# ledboard_smallcon.net
KiCad netlist of a schematic drawn in EAGLE
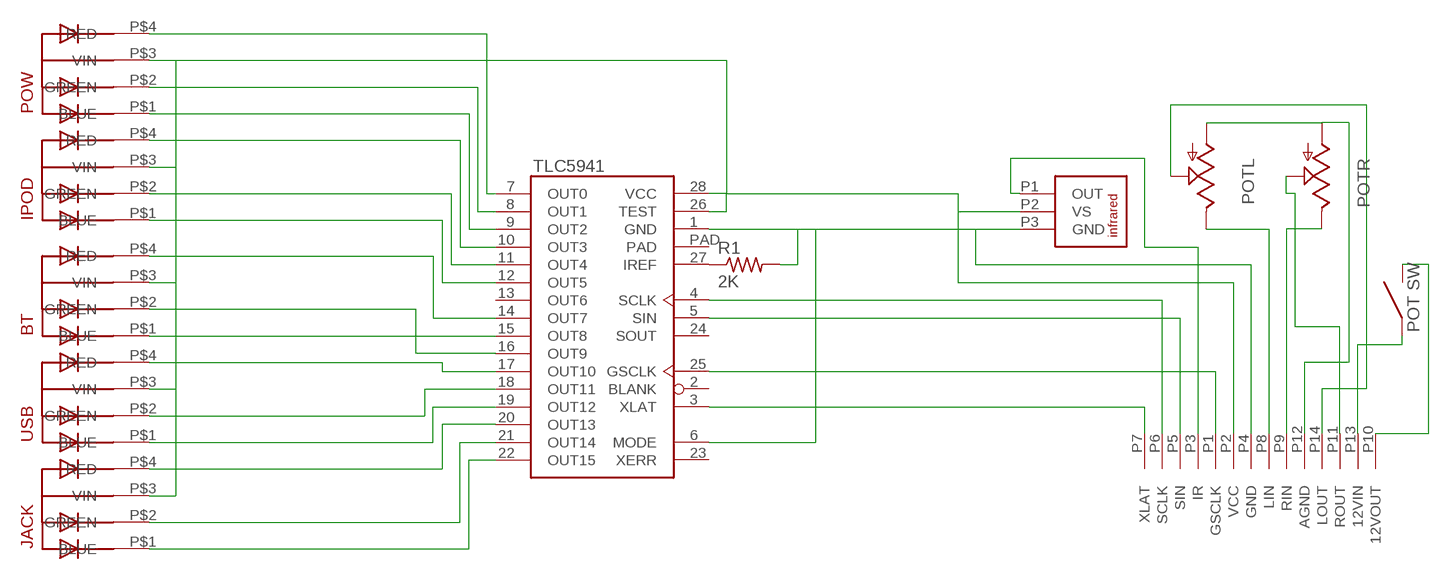
[diagram p0: schematic, sheet 1]

(export (version "E")
  (design (tool "Eeschema 10.0.6"))
  (components
    (comp (ref "BT")
      (value "5MMRGBLEDBENT")
      (footprint "eagle-import:BENTLED")
      (libsource (lib "eagle-import") (part "5MMRGBLEDBENT"))
    )
    (comp (ref "IPOD")
      (value "5MMRGBLEDBENT")
      (footprint "eagle-import:BENTLED")
      (libsource (lib "eagle-import") (part "5MMRGBLEDBENT"))
    )
    (comp (ref "IR")
      (value "TSOP323")
      (footprint "eagle-import:TSOP323")
      (libsource (lib "eagle-import") (part "TSOP323"))
    )
    (comp (ref "JACK")
      (value "5MMRGBLEDBENT")
      (footprint "eagle-import:BENTLED")
      (libsource (lib "eagle-import") (part "5MMRGBLEDBENT"))
    )
    (comp (ref "POT")
      (value "ALPS_RK0971221Z0N")
      (footprint "eagle-import:ALPS_RK0971221Z0X")
      (libsource (lib "eagle-import") (part "ALPS_RK0971221Z0N"))
    )
    (comp (ref "POW")
      (value "5MMRGBLEDBENT")
      (footprint "eagle-import:BENTLED")
      (libsource (lib "eagle-import") (part "5MMRGBLEDBENT"))
    )
    (comp (ref "R1")
      (value "2K")
      (footprint "eagle-import:0207_7")
      (libsource (lib "eagle-import") (part "R-US_0207/7"))
    )
    (comp (ref "U$1")
      (value "TLC5941")
      (footprint "eagle-import:HTSSOP28_POWERPAD")
      (libsource (lib "eagle-import") (part "TLC5941"))
    )
    (comp (ref "U$3")
      (value "CONNECTORSMALL")
      (footprint "eagle-import:CON2")
      (libsource (lib "eagle-import") (part "CONNECTORSMALL"))
    )
    (comp (ref "USB")
      (value "5MMRGBLEDBENT")
      (footprint "eagle-import:BENTLED")
      (libsource (lib "eagle-import") (part "5MMRGBLEDBENT"))
    )
  )
  (nets
    (net (code "1") (name "Net-(BT-BLUE)") (class "Default")
      (node (ref "BT") (pin "P$1") (pinfunction "BLUE_P$1") (pintype "bidirectional"))
      (node (ref "U$1") (pin "15") (pinfunction "OUT8_15") (pintype "output"))
    )
    (net (code "2") (name "Net-(BT-GREEN)") (class "Default")
      (node (ref "BT") (pin "P$2") (pinfunction "GREEN_P$2") (pintype "bidirectional"))
      (node (ref "U$1") (pin "16") (pinfunction "OUT9_16") (pintype "output"))
    )
    (net (code "3") (name "Net-(BT-RED)") (class "Default")
      (node (ref "BT") (pin "P$4") (pinfunction "RED_P$4") (pintype "bidirectional"))
      (node (ref "U$1") (pin "14") (pinfunction "OUT7_14") (pintype "output"))
    )
    (net (code "4") (name "Net-(BT-VIN)") (class "Default")
      (node (ref "BT") (pin "P$3") (pinfunction "VIN_P$3") (pintype "bidirectional"))
      (node (ref "IPOD") (pin "P$3") (pinfunction "VIN_P$3") (pintype "bidirectional"))
      (node (ref "IR") (pin "P2") (pinfunction "VS_P2") (pintype "bidirectional"))
      (node (ref "JACK") (pin "P$3") (pinfunction "VIN_P$3") (pintype "bidirectional"))
      (node (ref "POW") (pin "P$3") (pinfunction "VIN_P$3") (pintype "bidirectional"))
      (node (ref "U$1") (pin "26") (pinfunction "TEST_26") (pintype "bidirectional"))
      (node (ref "U$1") (pin "28") (pinfunction "VCC_28") (pintype "power_in"))
      (node (ref "U$3") (pin "P2") (pinfunction "VCC_P2") (pintype "bidirectional"))
      (node (ref "USB") (pin "P$3") (pinfunction "VIN_P$3") (pintype "bidirectional"))
    )
    (net (code "5") (name "Net-(IPOD-BLUE)") (class "Default")
      (node (ref "IPOD") (pin "P$1") (pinfunction "BLUE_P$1") (pintype "bidirectional"))
      (node (ref "U$1") (pin "12") (pinfunction "OUT5_12") (pintype "output"))
    )
    (net (code "6") (name "Net-(IPOD-GREEN)") (class "Default")
      (node (ref "IPOD") (pin "P$2") (pinfunction "GREEN_P$2") (pintype "bidirectional"))
      (node (ref "U$1") (pin "11") (pinfunction "OUT4_11") (pintype "output"))
    )
    (net (code "7") (name "Net-(IPOD-RED)") (class "Default")
      (node (ref "IPOD") (pin "P$4") (pinfunction "RED_P$4") (pintype "bidirectional"))
      (node (ref "U$1") (pin "10") (pinfunction "OUT3_10") (pintype "output"))
    )
    (net (code "8") (name "Net-(IR-GND)") (class "Default")
      (node (ref "IR") (pin "P3") (pinfunction "GND_P3") (pintype "bidirectional"))
      (node (ref "R1") (pin "2") (pinfunction "2_2") (pintype "passive"))
      (node (ref "U$1") (pin "1") (pinfunction "GND_1") (pintype "power_in"))
      (node (ref "U$1") (pin "6") (pinfunction "MODE_6") (pintype "bidirectional"))
      (node (ref "U$3") (pin "P4") (pinfunction "GND_P4") (pintype "bidirectional"))
    )
    (net (code "9") (name "Net-(IR-OUT)") (class "Default")
      (node (ref "IR") (pin "P1") (pinfunction "OUT_P1") (pintype "bidirectional"))
      (node (ref "U$3") (pin "P3") (pinfunction "IR_P3") (pintype "bidirectional"))
    )
    (net (code "10") (name "Net-(JACK-BLUE)") (class "Default")
      (node (ref "JACK") (pin "P$1") (pinfunction "BLUE_P$1") (pintype "bidirectional"))
      (node (ref "U$1") (pin "22") (pinfunction "OUT15_22") (pintype "output"))
    )
    (net (code "11") (name "Net-(JACK-GREEN)") (class "Default")
      (node (ref "JACK") (pin "P$2") (pinfunction "GREEN_P$2") (pintype "bidirectional"))
      (node (ref "U$1") (pin "21") (pinfunction "OUT14_21") (pintype "output"))
    )
    (net (code "12") (name "Net-(JACK-RED)") (class "Default")
      (node (ref "JACK") (pin "P$4") (pinfunction "RED_P$4") (pintype "bidirectional"))
      (node (ref "U$1") (pin "20") (pinfunction "OUT13_20") (pintype "output"))
    )
    (net (code "13") (name "Net-(POTB-1)") (class "Default")
      (node (ref "POT") (pin "G1") (pinfunction "1_G1") (pintype "passive"))
      (node (ref "POT") (pin "G2") (pinfunction "1_G2") (pintype "passive"))
      (node (ref "U$3") (pin "P12") (pinfunction "AGND_P12") (pintype "bidirectional"))
    )
    (net (code "14") (name "Net-(POTB-2)") (class "Default")
      (node (ref "POT") (pin "O1") (pinfunction "2_O1") (pintype "passive"))
      (node (ref "U$3") (pin "P14") (pinfunction "LOUT_P14") (pintype "bidirectional"))
    )
    (net (code "15") (name "Net-(POTB-3)") (class "Default")
      (node (ref "POT") (pin "I1") (pinfunction "3_I1") (pintype "passive"))
      (node (ref "U$3") (pin "P8") (pinfunction "LIN_P8") (pintype "bidirectional"))
    )
    (net (code "16") (name "Net-(POTC-2)") (class "Default")
      (node (ref "POT") (pin "O2") (pinfunction "2_O2") (pintype "passive"))
      (node (ref "U$3") (pin "P11") (pinfunction "ROUT_P11") (pintype "bidirectional"))
    )
    (net (code "17") (name "Net-(POTC-3)") (class "Default")
      (node (ref "POT") (pin "I2") (pinfunction "3_I2") (pintype "passive"))
      (node (ref "U$3") (pin "P9") (pinfunction "RIN_P9") (pintype "bidirectional"))
    )
    (net (code "18") (name "Net-(POW-BLUE)") (class "Default")
      (node (ref "POW") (pin "P$1") (pinfunction "BLUE_P$1") (pintype "bidirectional"))
      (node (ref "U$1") (pin "9") (pinfunction "OUT2_9") (pintype "output"))
    )
    (net (code "19") (name "Net-(POW-GREEN)") (class "Default")
      (node (ref "POW") (pin "P$2") (pinfunction "GREEN_P$2") (pintype "bidirectional"))
      (node (ref "U$1") (pin "8") (pinfunction "OUT1_8") (pintype "output"))
    )
    (net (code "20") (name "Net-(POW-RED)") (class "Default")
      (node (ref "POW") (pin "P$4") (pinfunction "RED_P$4") (pintype "bidirectional"))
      (node (ref "U$1") (pin "7") (pinfunction "OUT0_7") (pintype "output"))
    )
    (net (code "21") (name "Net-(U$1-GSCLK)") (class "Default")
      (node (ref "U$1") (pin "25") (pinfunction "GSCLK_25") (pintype "input"))
      (node (ref "U$3") (pin "P1") (pinfunction "GSCLK_P1") (pintype "bidirectional"))
    )
    (net (code "22") (name "Net-(U$1-IREF)") (class "Default")
      (node (ref "R1") (pin "1") (pinfunction "1_1") (pintype "passive"))
      (node (ref "U$1") (pin "27") (pinfunction "IREF_27") (pintype "input"))
    )
    (net (code "23") (name "Net-(U$1-OUT10)") (class "Default")
      (node (ref "U$1") (pin "17") (pinfunction "OUT10_17") (pintype "output"))
      (node (ref "USB") (pin "P$4") (pinfunction "RED_P$4") (pintype "bidirectional"))
    )
    (net (code "24") (name "Net-(U$1-OUT11)") (class "Default")
      (node (ref "U$1") (pin "18") (pinfunction "OUT11_18") (pintype "output"))
      (node (ref "USB") (pin "P$2") (pinfunction "GREEN_P$2") (pintype "bidirectional"))
    )
    (net (code "25") (name "Net-(U$1-OUT12)") (class "Default")
      (node (ref "U$1") (pin "19") (pinfunction "OUT12_19") (pintype "output"))
      (node (ref "USB") (pin "P$1") (pinfunction "BLUE_P$1") (pintype "bidirectional"))
    )
    (net (code "26") (name "Net-(U$1-SCLK)") (class "Default")
      (node (ref "U$1") (pin "4") (pinfunction "SCLK_4") (pintype "input"))
      (node (ref "U$3") (pin "P6") (pinfunction "SCLK_P6") (pintype "bidirectional"))
    )
    (net (code "27") (name "Net-(U$1-SIN)") (class "Default")
      (node (ref "U$1") (pin "5") (pinfunction "SIN_5") (pintype "input"))
      (node (ref "U$3") (pin "P5") (pinfunction "SIN_P5") (pintype "bidirectional"))
    )
    (net (code "28") (name "Net-(U$1-XLAT)") (class "Default")
      (node (ref "U$1") (pin "3") (pinfunction "XLAT_3") (pintype "input"))
      (node (ref "U$3") (pin "P7") (pinfunction "XLAT_P7") (pintype "bidirectional"))
    )
    (net (code "29") (name "Net-(U$3-12VIN)") (class "Default")
      (node (ref "POT") (pin "S1") (pinfunction "S1_S1") (pintype "power_in"))
      (node (ref "U$3") (pin "P13") (pinfunction "12VIN_P13") (pintype "bidirectional"))
    )
    (net (code "30") (name "Net-(U$3-12VOUT)") (class "Default")
      (node (ref "POT") (pin "S2") (pinfunction "S2_S2") (pintype "power_in"))
      (node (ref "U$3") (pin "P10") (pinfunction "12VOUT_P10") (pintype "bidirectional"))
    )
    (net (code "31") (name "unconnected-(U$1-BLANK-Pad2)") (class "Default")
      (node (ref "U$1") (pin "2") (pinfunction "BLANK_2") (pintype "input"))
    )
    (net (code "32") (name "unconnected-(U$1-OUT6-Pad13)") (class "Default")
      (node (ref "U$1") (pin "13") (pinfunction "OUT6_13") (pintype "output"))
    )
    (net (code "33") (name "unconnected-(U$1-PadPAD)") (class "Default")
      (node (ref "U$1") (pin "PAD") (pinfunction "PAD_PAD") (pintype "bidirectional"))
    )
    (net (code "34") (name "unconnected-(U$1-SOUT-Pad24)") (class "Default")
      (node (ref "U$1") (pin "24") (pinfunction "SOUT_24") (pintype "output"))
    )
    (net (code "35") (name "unconnected-(U$1-XERR-Pad23)") (class "Default")
      (node (ref "U$1") (pin "23") (pinfunction "XERR_23") (pintype "output"))
    )
  )
)
